# AudioBoard4.net
KiCad netlist of a schematic drawn in EAGLE
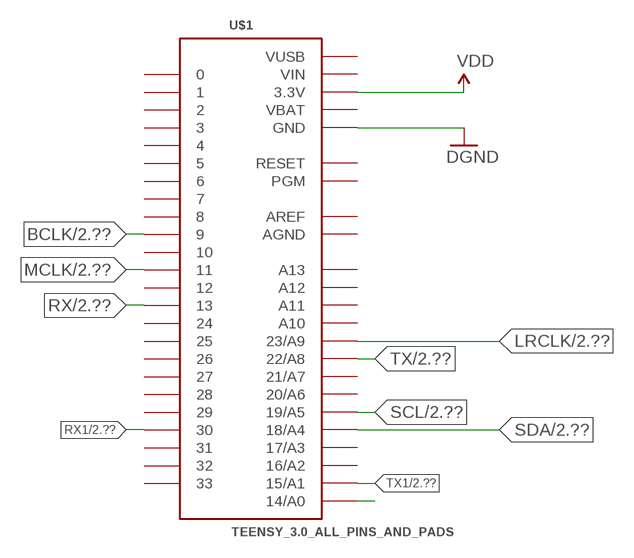
[diagram p0: schematic, sheet 1]
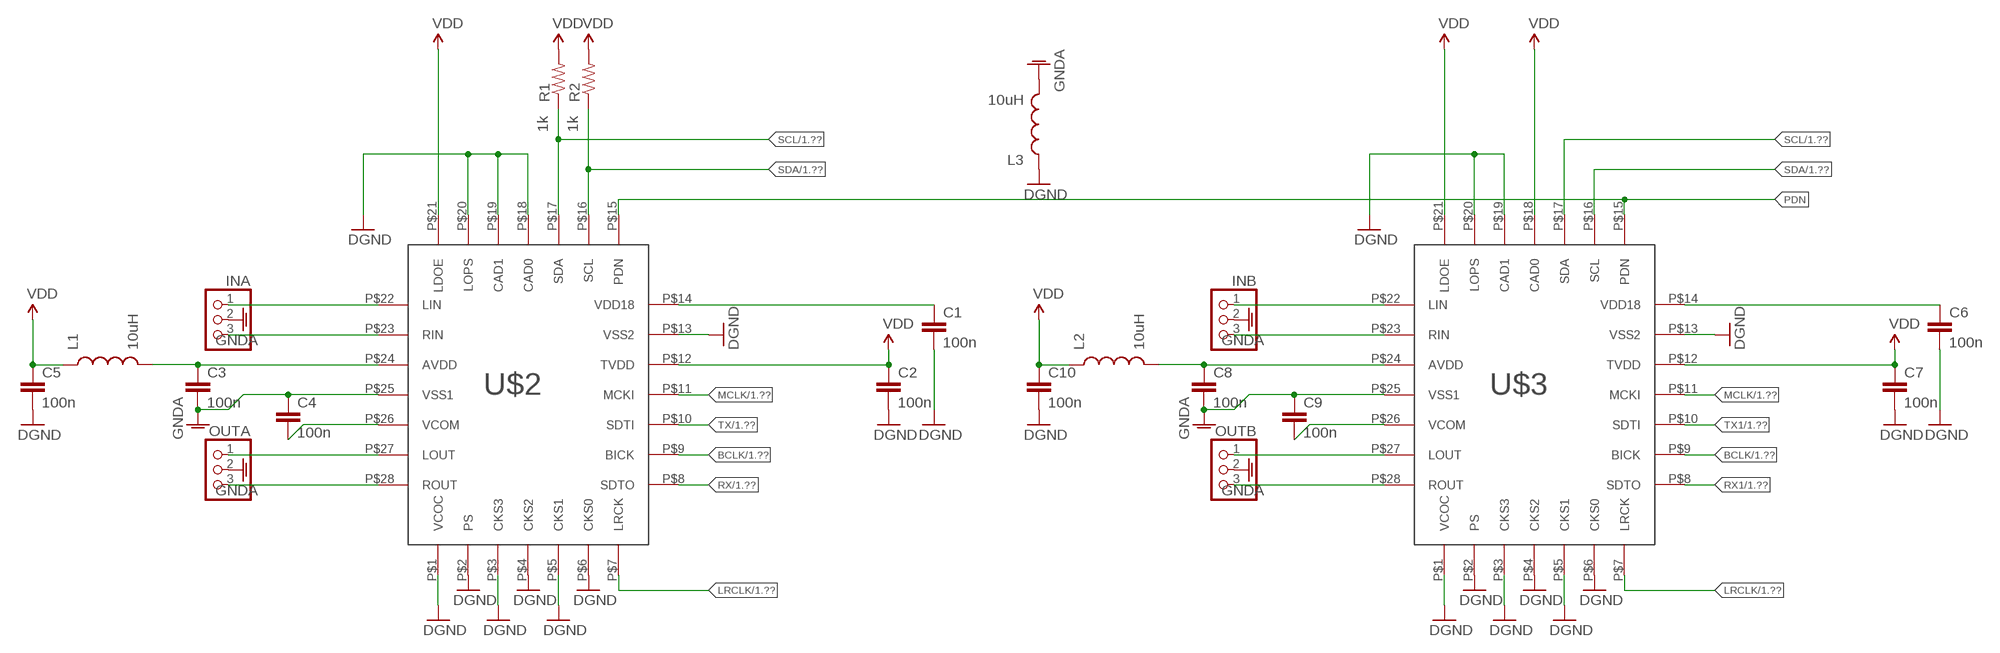
[diagram p1: schematic, sheet 2]

(export (version "E")
  (design (tool "Eeschema 10.0.6"))
  (components
    (comp (ref "C1")
      (value "100n")
      (footprint "eagle-import:0603-CAP")
      (libsource (lib "eagle-import") (part "CAP0603-CAP"))
    )
    (comp (ref "C2")
      (value "100n")
      (footprint "eagle-import:0603-CAP")
      (libsource (lib "eagle-import") (part "CAP0603-CAP"))
    )
    (comp (ref "C3")
      (value "100n")
      (footprint "eagle-import:0603-CAP")
      (libsource (lib "eagle-import") (part "CAP0603-CAP"))
    )
    (comp (ref "C4")
      (value "100n")
      (footprint "eagle-import:0603-CAP")
      (libsource (lib "eagle-import") (part "CAP0603-CAP"))
    )
    (comp (ref "C5")
      (value "100n")
      (footprint "eagle-import:0603-CAP")
      (libsource (lib "eagle-import") (part "CAP0603-CAP"))
    )
    (comp (ref "C6")
      (value "100n")
      (footprint "eagle-import:0603-CAP")
      (libsource (lib "eagle-import") (part "CAP0603-CAP"))
    )
    (comp (ref "C7")
      (value "100n")
      (footprint "eagle-import:0603-CAP")
      (libsource (lib "eagle-import") (part "CAP0603-CAP"))
    )
    (comp (ref "C8")
      (value "100n")
      (footprint "eagle-import:0603-CAP")
      (libsource (lib "eagle-import") (part "CAP0603-CAP"))
    )
    (comp (ref "C9")
      (value "100n")
      (footprint "eagle-import:0603-CAP")
      (libsource (lib "eagle-import") (part "CAP0603-CAP"))
    )
    (comp (ref "C10")
      (value "100n")
      (footprint "eagle-import:0603-CAP")
      (libsource (lib "eagle-import") (part "CAP0603-CAP"))
    )
    (comp (ref "INA")
      (value "PINHD-1X3")
      (footprint "eagle-import:1X03")
      (libsource (lib "eagle-import") (part "PINHD-1X3"))
    )
    (comp (ref "INB")
      (value "PINHD-1X3")
      (footprint "eagle-import:1X03")
      (libsource (lib "eagle-import") (part "PINHD-1X3"))
    )
    (comp (ref "L1")
      (value "10uH")
      (footprint "eagle-import:0805")
      (libsource (lib "eagle-import") (part "INDUCTOR0805"))
    )
    (comp (ref "L2")
      (value "10uH")
      (footprint "eagle-import:0805")
      (libsource (lib "eagle-import") (part "INDUCTOR0805"))
    )
    (comp (ref "L3")
      (value "10uH")
      (footprint "eagle-import:0603")
      (libsource (lib "eagle-import") (part "INDUCTOR0603"))
    )
    (comp (ref "OUTA")
      (value "PINHD-1X3")
      (footprint "eagle-import:1X03")
      (libsource (lib "eagle-import") (part "PINHD-1X3"))
    )
    (comp (ref "OUTB")
      (value "PINHD-1X3")
      (footprint "eagle-import:1X03")
      (libsource (lib "eagle-import") (part "PINHD-1X3"))
    )
    (comp (ref "R1")
      (value "1k")
      (footprint "eagle-import:0603-RES")
      (libsource (lib "eagle-import") (part "RESISTOR0603-RES"))
    )
    (comp (ref "R2")
      (value "1k")
      (footprint "eagle-import:0603-RES")
      (libsource (lib "eagle-import") (part "RESISTOR0603-RES"))
    )
    (comp (ref "U$2")
      (value "AK4558EN")
      (footprint "eagle-import:QFN-28-5MM")
      (libsource (lib "eagle-import") (part "AK4558EN"))
    )
    (comp (ref "U$3")
      (value "AK4558EN")
      (footprint "eagle-import:QFN-28-5MM")
      (libsource (lib "eagle-import") (part "AK4558EN"))
    )
    (comp (ref "U$1")
      (value "TEENSY_3.0_ALL_PINS_AND_PADS")
      (footprint "eagle-import:TEENSY_3.0_ALLPINS")
      (libsource (lib "eagle-import") (part "TEENSY_3.0_ALL_PINS_AND_PADS"))
    )
  )
  (nets
    (net (code "1") (name "AGND") (class "Default")
      (node (ref "U$1") (pin "AGND") (pinfunction "AGND_AGND") (pintype "power_in"))
    )
    (net (code "2") (name "AREF") (class "Default")
      (node (ref "U$1") (pin "AREF") (pinfunction "AREF_AREF") (pintype "power_in"))
    )
    (net (code "3") (name "BCLK") (class "Default")
      (node (ref "U$1") (pin "9") (pinfunction "9_9") (pintype "bidirectional"))
      (node (ref "U$2") (pin "P$9") (pinfunction "BICK_P$9") (pintype "bidirectional"))
      (node (ref "U$3") (pin "P$9") (pinfunction "BICK_P$9") (pintype "bidirectional"))
    )
    (net (code "4") (name "GND") (class "Default")
      (node (ref "C1") (pin "2") (pinfunction "2_2") (pintype "passive"))
      (node (ref "C10") (pin "2") (pinfunction "2_2") (pintype "passive"))
      (node (ref "C2") (pin "2") (pinfunction "2_2") (pintype "passive"))
      (node (ref "C5") (pin "2") (pinfunction "2_2") (pintype "passive"))
      (node (ref "C6") (pin "2") (pinfunction "2_2") (pintype "passive"))
      (node (ref "C7") (pin "2") (pinfunction "2_2") (pintype "passive"))
      (node (ref "L3") (pin "1") (pinfunction "1_1") (pintype "passive"))
      (node (ref "U$1") (pin "GND") (pinfunction "GND_GND") (pintype "power_in"))
      (node (ref "U$1") (pin "GND1") (pinfunction "GND_GND1") (pintype "power_in"))
      (node (ref "U$1") (pin "GND2") (pinfunction "GND_GND2") (pintype "power_in"))
      (node (ref "U$2") (pin "P$1") (pinfunction "VCOC_P$1") (pintype "bidirectional"))
      (node (ref "U$2") (pin "P$13") (pinfunction "VSS2_P$13") (pintype "bidirectional"))
      (node (ref "U$2") (pin "P$18") (pinfunction "CAD0_P$18") (pintype "bidirectional"))
      (node (ref "U$2") (pin "P$19") (pinfunction "CAD1_P$19") (pintype "bidirectional"))
      (node (ref "U$2") (pin "P$2") (pinfunction "PS_P$2") (pintype "bidirectional"))
      (node (ref "U$2") (pin "P$20") (pinfunction "LOPS_P$20") (pintype "bidirectional"))
      (node (ref "U$2") (pin "P$3") (pinfunction "CKS3_P$3") (pintype "bidirectional"))
      (node (ref "U$2") (pin "P$4") (pinfunction "CKS2_P$4") (pintype "bidirectional"))
      (node (ref "U$2") (pin "P$5") (pinfunction "CKS1_P$5") (pintype "bidirectional"))
      (node (ref "U$2") (pin "P$6") (pinfunction "CKS0_P$6") (pintype "bidirectional"))
      (node (ref "U$3") (pin "P$1") (pinfunction "VCOC_P$1") (pintype "bidirectional"))
      (node (ref "U$3") (pin "P$13") (pinfunction "VSS2_P$13") (pintype "bidirectional"))
      (node (ref "U$3") (pin "P$19") (pinfunction "CAD1_P$19") (pintype "bidirectional"))
      (node (ref "U$3") (pin "P$2") (pinfunction "PS_P$2") (pintype "bidirectional"))
      (node (ref "U$3") (pin "P$20") (pinfunction "LOPS_P$20") (pintype "bidirectional"))
      (node (ref "U$3") (pin "P$3") (pinfunction "CKS3_P$3") (pintype "bidirectional"))
      (node (ref "U$3") (pin "P$4") (pinfunction "CKS2_P$4") (pintype "bidirectional"))
      (node (ref "U$3") (pin "P$5") (pinfunction "CKS1_P$5") (pintype "bidirectional"))
      (node (ref "U$3") (pin "P$6") (pinfunction "CKS0_P$6") (pintype "bidirectional"))
    )
    (net (code "5") (name "GNDA") (class "Default")
      (node (ref "C3") (pin "2") (pinfunction "2_2") (pintype "passive"))
      (node (ref "C4") (pin "1") (pinfunction "1_1") (pintype "passive"))
      (node (ref "C8") (pin "2") (pinfunction "2_2") (pintype "passive"))
      (node (ref "C9") (pin "1") (pinfunction "1_1") (pintype "passive"))
      (node (ref "INA") (pin "2") (pinfunction "2_2") (pintype "passive"))
      (node (ref "INB") (pin "2") (pinfunction "2_2") (pintype "passive"))
      (node (ref "L3") (pin "2") (pinfunction "2_2") (pintype "passive"))
      (node (ref "OUTA") (pin "2") (pinfunction "2_2") (pintype "passive"))
      (node (ref "OUTB") (pin "2") (pinfunction "2_2") (pintype "passive"))
      (node (ref "U$2") (pin "P$25") (pinfunction "VSS1_P$25") (pintype "bidirectional"))
      (node (ref "U$3") (pin "P$25") (pinfunction "VSS1_P$25") (pintype "bidirectional"))
    )
    (net (code "6") (name "LRCLK") (class "Default")
      (node (ref "U$1") (pin "23/A9") (pinfunction "23/A9_23/A9") (pintype "bidirectional"))
      (node (ref "U$2") (pin "P$7") (pinfunction "LRCK_P$7") (pintype "bidirectional"))
      (node (ref "U$3") (pin "P$7") (pinfunction "LRCK_P$7") (pintype "bidirectional"))
    )
    (net (code "7") (name "MCLK") (class "Default")
      (node (ref "U$1") (pin "11") (pinfunction "11_11") (pintype "bidirectional"))
      (node (ref "U$2") (pin "P$11") (pinfunction "MCKI_P$11") (pintype "bidirectional"))
      (node (ref "U$3") (pin "P$11") (pinfunction "MCKI_P$11") (pintype "bidirectional"))
    )
    (net (code "8") (name "Net-(U$2-AVDD)") (class "Default")
      (node (ref "C3") (pin "1") (pinfunction "1_1") (pintype "passive"))
      (node (ref "L1") (pin "2") (pinfunction "2_2") (pintype "passive"))
      (node (ref "U$2") (pin "P$24") (pinfunction "AVDD_P$24") (pintype "bidirectional"))
    )
    (net (code "9") (name "Net-(U$2-LIN)") (class "Default")
      (node (ref "INA") (pin "1") (pinfunction "1_1") (pintype "passive"))
      (node (ref "U$2") (pin "P$22") (pinfunction "LIN_P$22") (pintype "bidirectional"))
    )
    (net (code "10") (name "Net-(U$2-LOUT)") (class "Default")
      (node (ref "OUTA") (pin "1") (pinfunction "1_1") (pintype "passive"))
      (node (ref "U$2") (pin "P$27") (pinfunction "LOUT_P$27") (pintype "bidirectional"))
    )
    (net (code "11") (name "Net-(U$2-RIN)") (class "Default")
      (node (ref "INA") (pin "3") (pinfunction "3_3") (pintype "passive"))
      (node (ref "U$2") (pin "P$23") (pinfunction "RIN_P$23") (pintype "bidirectional"))
    )
    (net (code "12") (name "Net-(U$2-ROUT)") (class "Default")
      (node (ref "OUTA") (pin "3") (pinfunction "3_3") (pintype "passive"))
      (node (ref "U$2") (pin "P$28") (pinfunction "ROUT_P$28") (pintype "bidirectional"))
    )
    (net (code "13") (name "Net-(U$2-VCOM)") (class "Default")
      (node (ref "C4") (pin "2") (pinfunction "2_2") (pintype "passive"))
      (node (ref "U$2") (pin "P$26") (pinfunction "VCOM_P$26") (pintype "bidirectional"))
    )
    (net (code "14") (name "Net-(U$2-VDD18)") (class "Default")
      (node (ref "C1") (pin "1") (pinfunction "1_1") (pintype "passive"))
      (node (ref "U$2") (pin "P$14") (pinfunction "VDD18_P$14") (pintype "bidirectional"))
    )
    (net (code "15") (name "Net-(U$3-AVDD)") (class "Default")
      (node (ref "C8") (pin "1") (pinfunction "1_1") (pintype "passive"))
      (node (ref "L2") (pin "2") (pinfunction "2_2") (pintype "passive"))
      (node (ref "U$3") (pin "P$24") (pinfunction "AVDD_P$24") (pintype "bidirectional"))
    )
    (net (code "16") (name "Net-(U$3-LIN)") (class "Default")
      (node (ref "INB") (pin "1") (pinfunction "1_1") (pintype "passive"))
      (node (ref "U$3") (pin "P$22") (pinfunction "LIN_P$22") (pintype "bidirectional"))
    )
    (net (code "17") (name "Net-(U$3-LOUT)") (class "Default")
      (node (ref "OUTB") (pin "1") (pinfunction "1_1") (pintype "passive"))
      (node (ref "U$3") (pin "P$27") (pinfunction "LOUT_P$27") (pintype "bidirectional"))
    )
    (net (code "18") (name "Net-(U$3-RIN)") (class "Default")
      (node (ref "INB") (pin "3") (pinfunction "3_3") (pintype "passive"))
      (node (ref "U$3") (pin "P$23") (pinfunction "RIN_P$23") (pintype "bidirectional"))
    )
    (net (code "19") (name "Net-(U$3-ROUT)") (class "Default")
      (node (ref "OUTB") (pin "3") (pinfunction "3_3") (pintype "passive"))
      (node (ref "U$3") (pin "P$28") (pinfunction "ROUT_P$28") (pintype "bidirectional"))
    )
    (net (code "20") (name "Net-(U$3-VCOM)") (class "Default")
      (node (ref "C9") (pin "2") (pinfunction "2_2") (pintype "passive"))
      (node (ref "U$3") (pin "P$26") (pinfunction "VCOM_P$26") (pintype "bidirectional"))
    )
    (net (code "21") (name "Net-(U$3-VDD18)") (class "Default")
      (node (ref "C6") (pin "1") (pinfunction "1_1") (pintype "passive"))
      (node (ref "U$3") (pin "P$14") (pinfunction "VDD18_P$14") (pintype "bidirectional"))
    )
    (net (code "22") (name "PDN") (class "Default")
      (node (ref "U$1") (pin "14/A0") (pinfunction "14/A0_14/A0") (pintype "bidirectional"))
      (node (ref "U$2") (pin "P$15") (pinfunction "PDN_P$15") (pintype "bidirectional"))
      (node (ref "U$3") (pin "P$15") (pinfunction "PDN_P$15") (pintype "bidirectional"))
    )
    (net (code "23") (name "RX") (class "Default")
      (node (ref "U$1") (pin "13") (pinfunction "13_13") (pintype "bidirectional"))
      (node (ref "U$2") (pin "P$8") (pinfunction "SDTO_P$8") (pintype "bidirectional"))
    )
    (net (code "24") (name "RX1") (class "Default")
      (node (ref "U$1") (pin "30") (pinfunction "30_30") (pintype "bidirectional"))
      (node (ref "U$3") (pin "P$8") (pinfunction "SDTO_P$8") (pintype "bidirectional"))
    )
    (net (code "25") (name "SCL") (class "Default")
      (node (ref "R1") (pin "1") (pinfunction "1_1") (pintype "passive"))
      (node (ref "U$1") (pin "19/A5") (pinfunction "19/A5_19/A5") (pintype "bidirectional"))
      (node (ref "U$2") (pin "P$17") (pinfunction "SDA_P$17") (pintype "bidirectional"))
      (node (ref "U$3") (pin "P$17") (pinfunction "SDA_P$17") (pintype "bidirectional"))
    )
    (net (code "26") (name "SDA") (class "Default")
      (node (ref "R2") (pin "1") (pinfunction "1_1") (pintype "passive"))
      (node (ref "U$1") (pin "18/A4") (pinfunction "18/A4_18/A4") (pintype "bidirectional"))
      (node (ref "U$2") (pin "P$16") (pinfunction "SCL_P$16") (pintype "bidirectional"))
      (node (ref "U$3") (pin "P$16") (pinfunction "SCL_P$16") (pintype "bidirectional"))
    )
    (net (code "27") (name "TX") (class "Default")
      (node (ref "U$1") (pin "22/A8") (pinfunction "22/A8_22/A8") (pintype "bidirectional"))
      (node (ref "U$2") (pin "P$10") (pinfunction "SDTI_P$10") (pintype "bidirectional"))
    )
    (net (code "28") (name "TX1") (class "Default")
      (node (ref "U$1") (pin "15/A1") (pinfunction "15/A1_15/A1") (pintype "bidirectional"))
      (node (ref "U$3") (pin "P$10") (pinfunction "SDTI_P$10") (pintype "bidirectional"))
    )
    (net (code "29") (name "VBAT") (class "Default")
      (node (ref "U$1") (pin "VBAT") (pinfunction "VBAT_VBAT") (pintype "power_in"))
    )
    (net (code "30") (name "VDD") (class "Default")
      (node (ref "C10") (pin "1") (pinfunction "1_1") (pintype "passive"))
      (node (ref "C2") (pin "1") (pinfunction "1_1") (pintype "passive"))
      (node (ref "C5") (pin "1") (pinfunction "1_1") (pintype "passive"))
      (node (ref "C7") (pin "1") (pinfunction "1_1") (pintype "passive"))
      (node (ref "L1") (pin "1") (pinfunction "1_1") (pintype "passive"))
      (node (ref "L2") (pin "1") (pinfunction "1_1") (pintype "passive"))
      (node (ref "R1") (pin "2") (pinfunction "2_2") (pintype "passive"))
      (node (ref "R2") (pin "2") (pinfunction "2_2") (pintype "passive"))
      (node (ref "U$1") (pin "3.3V") (pinfunction "3.3V_3.3V") (pintype "power_in"))
      (node (ref "U$1") (pin "3.3V1") (pinfunction "3.3V_3.3V1") (pintype "power_in"))
      (node (ref "U$1") (pin "3.3V2") (pinfunction "3.3V_3.3V2") (pintype "power_in"))
      (node (ref "U$2") (pin "P$12") (pinfunction "TVDD_P$12") (pintype "bidirectional"))
      (node (ref "U$2") (pin "P$21") (pinfunction "LDOE_P$21") (pintype "bidirectional"))
      (node (ref "U$3") (pin "P$12") (pinfunction "TVDD_P$12") (pintype "bidirectional"))
      (node (ref "U$3") (pin "P$18") (pinfunction "CAD0_P$18") (pintype "bidirectional"))
      (node (ref "U$3") (pin "P$21") (pinfunction "LDOE_P$21") (pintype "bidirectional"))
    )
    (net (code "31") (name "VIN") (class "Default")
      (node (ref "U$1") (pin "VIN") (pinfunction "VIN_VIN") (pintype "power_in"))
    )
    (net (code "32") (name "VUSB") (class "Default")
      (node (ref "U$1") (pin "VUSB") (pinfunction "VUSB_VUSB") (pintype "power_in"))
    )
    (net (code "33") (name "unconnected-(U$1-Pad0)") (class "Default")
      (node (ref "U$1") (pin "0") (pinfunction "0_0") (pintype "bidirectional"))
    )
    (net (code "34") (name "unconnected-(U$1-Pad1)") (class "Default")
      (node (ref "U$1") (pin "1") (pinfunction "1_1") (pintype "bidirectional"))
    )
    (net (code "35") (name "unconnected-(U$1-Pad2)") (class "Default")
      (node (ref "U$1") (pin "2") (pinfunction "2_2") (pintype "bidirectional"))
    )
    (net (code "36") (name "unconnected-(U$1-Pad3)") (class "Default")
      (node (ref "U$1") (pin "3") (pinfunction "3_3") (pintype "bidirectional"))
    )
    (net (code "37") (name "unconnected-(U$1-Pad4)") (class "Default")
      (node (ref "U$1") (pin "4") (pinfunction "4_4") (pintype "bidirectional"))
    )
    (net (code "38") (name "unconnected-(U$1-Pad5)") (class "Default")
      (node (ref "U$1") (pin "5") (pinfunction "5_5") (pintype "bidirectional"))
    )
    (net (code "39") (name "unconnected-(U$1-Pad6)") (class "Default")
      (node (ref "U$1") (pin "6") (pinfunction "6_6") (pintype "bidirectional"))
    )
    (net (code "40") (name "unconnected-(U$1-Pad7)") (class "Default")
      (node (ref "U$1") (pin "7") (pinfunction "7_7") (pintype "bidirectional"))
    )
    (net (code "41") (name "unconnected-(U$1-Pad8)") (class "Default")
      (node (ref "U$1") (pin "8") (pinfunction "8_8") (pintype "bidirectional"))
    )
    (net (code "42") (name "unconnected-(U$1-Pad10)") (class "Default")
      (node (ref "U$1") (pin "10") (pinfunction "10_10") (pintype "bidirectional"))
    )
    (net (code "43") (name "unconnected-(U$1-Pad12)") (class "Default")
      (node (ref "U$1") (pin "12") (pinfunction "12_12") (pintype "bidirectional"))
    )
    (net (code "44") (name "unconnected-(U$1-Pad16{slash}A2)") (class "Default")
      (node (ref "U$1") (pin "16/A2") (pinfunction "16/A2_16/A2") (pintype "bidirectional"))
    )
    (net (code "45") (name "unconnected-(U$1-Pad17{slash}A3)") (class "Default")
      (node (ref "U$1") (pin "17/A3") (pinfunction "17/A3_17/A3") (pintype "bidirectional"))
    )
    (net (code "46") (name "unconnected-(U$1-Pad20{slash}A6)") (class "Default")
      (node (ref "U$1") (pin "20/A6") (pinfunction "20/A6_20/A6") (pintype "bidirectional"))
    )
    (net (code "47") (name "unconnected-(U$1-Pad21{slash}A7)") (class "Default")
      (node (ref "U$1") (pin "21/A7") (pinfunction "21/A7_21/A7") (pintype "bidirectional"))
    )
    (net (code "48") (name "unconnected-(U$1-Pad24)") (class "Default")
      (node (ref "U$1") (pin "24") (pinfunction "24_24") (pintype "bidirectional"))
    )
    (net (code "49") (name "unconnected-(U$1-Pad25)") (class "Default")
      (node (ref "U$1") (pin "25") (pinfunction "25_25") (pintype "bidirectional"))
    )
    (net (code "50") (name "unconnected-(U$1-Pad26)") (class "Default")
      (node (ref "U$1") (pin "26") (pinfunction "26_26") (pintype "bidirectional"))
    )
    (net (code "51") (name "unconnected-(U$1-Pad27)") (class "Default")
      (node (ref "U$1") (pin "27") (pinfunction "27_27") (pintype "bidirectional"))
    )
    (net (code "52") (name "unconnected-(U$1-Pad28)") (class "Default")
      (node (ref "U$1") (pin "28") (pinfunction "28_28") (pintype "bidirectional"))
    )
    (net (code "53") (name "unconnected-(U$1-Pad29)") (class "Default")
      (node (ref "U$1") (pin "29") (pinfunction "29_29") (pintype "bidirectional"))
    )
    (net (code "54") (name "unconnected-(U$1-Pad31)") (class "Default")
      (node (ref "U$1") (pin "31") (pinfunction "31_31") (pintype "bidirectional"))
    )
    (net (code "55") (name "unconnected-(U$1-Pad32)") (class "Default")
      (node (ref "U$1") (pin "32") (pinfunction "32_32") (pintype "bidirectional"))
    )
    (net (code "56") (name "unconnected-(U$1-Pad33)") (class "Default")
      (node (ref "U$1") (pin "33") (pinfunction "33_33") (pintype "bidirectional"))
    )
    (net (code "57") (name "unconnected-(U$1-PadA10)") (class "Default")
      (node (ref "U$1") (pin "A10") (pinfunction "A10_A10") (pintype "bidirectional"))
    )
    (net (code "58") (name "unconnected-(U$1-PadA11)") (class "Default")
      (node (ref "U$1") (pin "A11") (pinfunction "A11_A11") (pintype "bidirectional"))
    )
    (net (code "59") (name "unconnected-(U$1-PadA12)") (class "Default")
      (node (ref "U$1") (pin "A12") (pinfunction "A12_A12") (pintype "bidirectional"))
    )
    (net (code "60") (name "unconnected-(U$1-PadA13)") (class "Default")
      (node (ref "U$1") (pin "A13") (pinfunction "A13_A13") (pintype "bidirectional"))
    )
    (net (code "61") (name "unconnected-(U$1-PadPGM)") (class "Default")
      (node (ref "U$1") (pin "PGM") (pinfunction "PGM_PGM") (pintype "bidirectional"))
    )
    (net (code "62") (name "unconnected-(U$1-PadRESET)") (class "Default")
      (node (ref "U$1") (pin "RESET") (pinfunction "RESET_RESET") (pintype "bidirectional"))
    )
  )
)
